# control_AX12.net
KiCad netlist of a schematic drawn in EAGLE
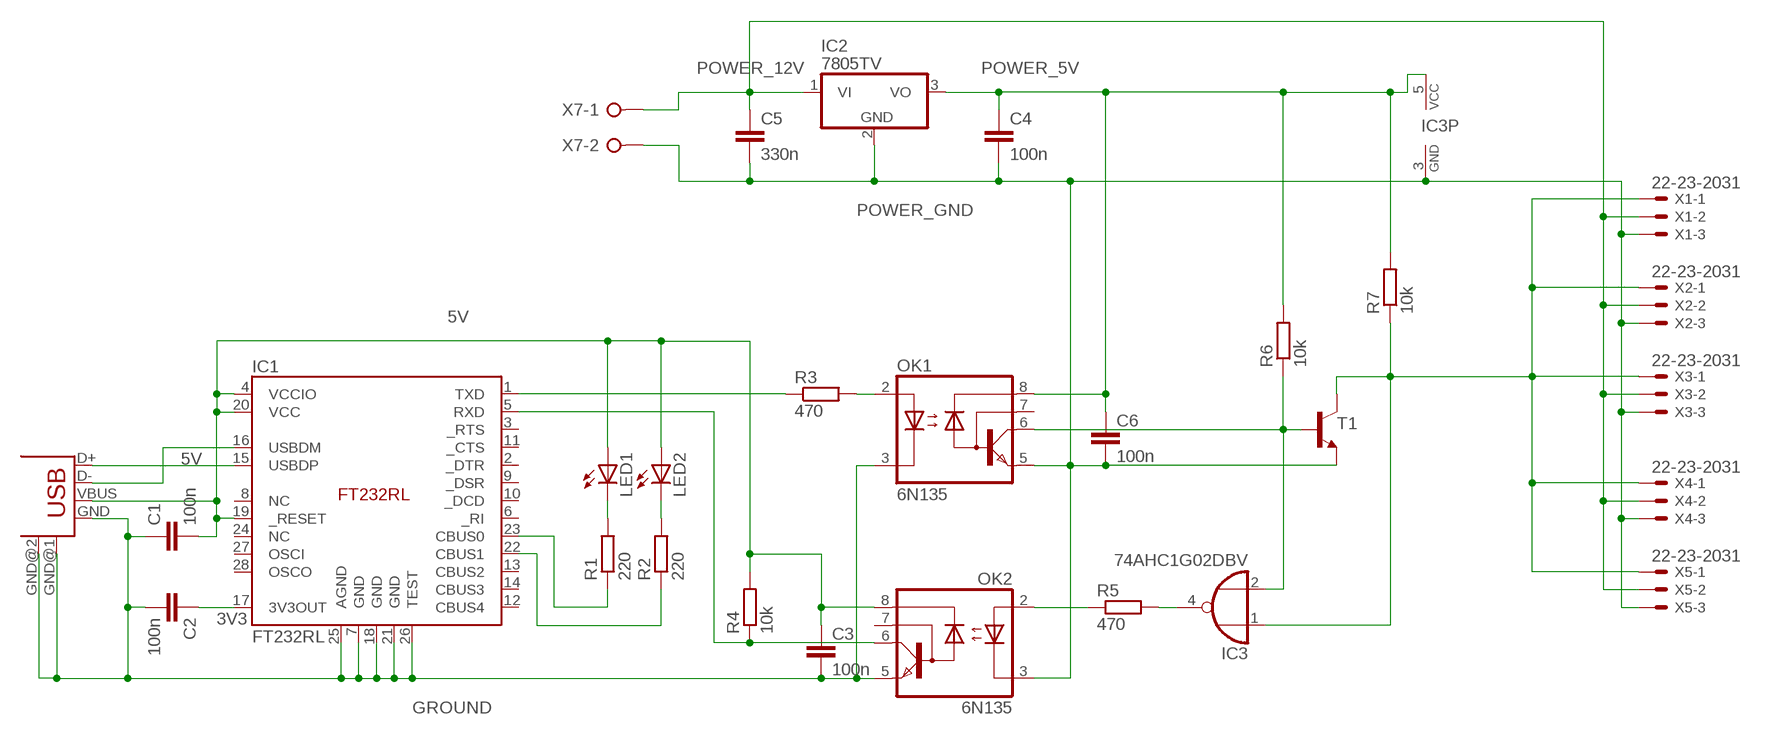
[diagram p0: schematic, sheet 1]

(export (version "E")
  (design (tool "Eeschema 10.0.6"))
  (components
    (comp (ref "C1")
      (value "100n")
      (footprint "eagle-import:C0805")
      (libsource (lib "eagle-import") (part "C-EUC0805"))
    )
    (comp (ref "C2")
      (value "100n")
      (footprint "eagle-import:C0805")
      (libsource (lib "eagle-import") (part "C-EUC0805"))
    )
    (comp (ref "C3")
      (value "100n")
      (footprint "eagle-import:C0805")
      (libsource (lib "eagle-import") (part "C-EUC0805"))
    )
    (comp (ref "C4")
      (value "100n")
      (footprint "eagle-import:C0805")
      (libsource (lib "eagle-import") (part "C-EUC0805"))
    )
    (comp (ref "C5")
      (value "330n")
      (footprint "eagle-import:C0805")
      (libsource (lib "eagle-import") (part "C-EUC0805"))
    )
    (comp (ref "C6")
      (value "100n")
      (footprint "eagle-import:C0805")
      (libsource (lib "eagle-import") (part "C-EUC0805"))
    )
    (comp (ref "IC1")
      (value "FT232RL")
      (footprint "eagle-import:SSOP-28")
      (libsource (lib "eagle-import") (part "FT232RL"))
    )
    (comp (ref "IC2")
      (value "7805TV")
      (footprint "eagle-import:TO220V")
      (libsource (lib "eagle-import") (part "78TV05"))
    )
    (comp (ref "IC3")
      (value "74AHC1G02DBV")
      (footprint "eagle-import:SOT23-5")
      (libsource (lib "eagle-import") (part "741G02DBVAHC"))
    )
    (comp (ref "LED1")
      (value "LED5MM")
      (footprint "eagle-import:LED5MM")
      (libsource (lib "eagle-import") (part "LED5MM"))
    )
    (comp (ref "LED2")
      (value "LED5MM")
      (footprint "eagle-import:LED5MM")
      (libsource (lib "eagle-import") (part "LED5MM"))
    )
    (comp (ref "OK1")
      (value "6N135")
      (footprint "eagle-import:DIL08")
      (fields (field (name "MF") "FAIRCHILD SEMICONDUCTOR"))
      (libsource (lib "eagle-import") (part "6N135"))
    )
    (comp (ref "OK2")
      (value "6N135")
      (footprint "eagle-import:DIL08")
      (fields (field (name "MF") "FAIRCHILD SEMICONDUCTOR"))
      (libsource (lib "eagle-import") (part "6N135"))
    )
    (comp (ref "R1")
      (value "220")
      (footprint "eagle-import:M0805")
      (libsource (lib "eagle-import") (part "resistor_R-EU_M0805"))
    )
    (comp (ref "R2")
      (value "220")
      (footprint "eagle-import:M0805")
      (libsource (lib "eagle-import") (part "resistor_R-EU_M0805"))
    )
    (comp (ref "R3")
      (value "470")
      (footprint "eagle-import:0207_10")
      (libsource (lib "eagle-import") (part "R-EU_0207/10"))
    )
    (comp (ref "R4")
      (value "10k")
      (footprint "eagle-import:0207_10")
      (libsource (lib "eagle-import") (part "R-EU_0207/10"))
    )
    (comp (ref "R5")
      (value "470")
      (footprint "eagle-import:0207_10")
      (libsource (lib "eagle-import") (part "R-EU_0207/10"))
    )
    (comp (ref "R6")
      (value "10k")
      (footprint "eagle-import:0207_10")
      (libsource (lib "eagle-import") (part "R-EU_0207/10"))
    )
    (comp (ref "R7")
      (value "10k")
      (footprint "eagle-import:0207_10")
      (libsource (lib "eagle-import") (part "R-EU_0207/10"))
    )
    (comp (ref "T1")
      (value "BC547-NPN-TO92-CBE")
      (footprint "eagle-import:TO92-CBE")
      (libsource (lib "eagle-import") (part "-NPN-TO92-CBEBC547"))
    )
    (comp (ref "USB1")
      (value "USB-B-H")
      (footprint "eagle-import:USB-B-H")
      (libsource (lib "eagle-import") (part "USB-B-H"))
    )
    (comp (ref "X1")
      (value "22-23-2031")
      (footprint "eagle-import:22-23-2031")
      (fields (field (name "MF") "MOLEX"))
      (libsource (lib "eagle-import") (part "22-23-2031"))
    )
    (comp (ref "X2")
      (value "22-23-2031")
      (footprint "eagle-import:22-23-2031")
      (fields (field (name "MF") "MOLEX"))
      (libsource (lib "eagle-import") (part "22-23-2031"))
    )
    (comp (ref "X3")
      (value "22-23-2031")
      (footprint "eagle-import:22-23-2031")
      (fields (field (name "MF") "MOLEX"))
      (libsource (lib "eagle-import") (part "22-23-2031"))
    )
    (comp (ref "X4")
      (value "22-23-2031")
      (footprint "eagle-import:22-23-2031")
      (fields (field (name "MF") "MOLEX"))
      (libsource (lib "eagle-import") (part "22-23-2031"))
    )
    (comp (ref "X5")
      (value "22-23-2031")
      (footprint "eagle-import:22-23-2031")
      (fields (field (name "MF") "MOLEX"))
      (libsource (lib "eagle-import") (part "22-23-2031"))
    )
    (comp (ref "X7")
      (value "W237-02P")
      (footprint "eagle-import:W237-132")
      (libsource (lib "eagle-import") (part "W237-02P"))
    )
  )
  (nets
    (net (code "1") (name "/3V3") (class "Default")
      (node (ref "C2") (pin "1") (pinfunction "1_1") (pintype "passive"))
      (node (ref "IC1") (pin "17") (pinfunction "3V3OUT_17") (pintype "output"))
    )
    (net (code "2") (name "/5V") (class "Default")
      (node (ref "C1") (pin "2") (pinfunction "2_2") (pintype "passive"))
      (node (ref "C3") (pin "1") (pinfunction "1_1") (pintype "passive"))
      (node (ref "IC1") (pin "19") (pinfunction "_RESET_19") (pintype "input"))
      (node (ref "IC1") (pin "20") (pinfunction "VCC_20") (pintype "power_in"))
      (node (ref "IC1") (pin "4") (pinfunction "VCCIO_4") (pintype "power_in"))
      (node (ref "LED1") (pin "A") (pinfunction "A_A") (pintype "passive"))
      (node (ref "LED2") (pin "A") (pinfunction "A_A") (pintype "passive"))
      (node (ref "OK2") (pin "8") (pinfunction "VCC_8") (pintype "passive"))
      (node (ref "R4") (pin "2") (pinfunction "2_2") (pintype "passive"))
      (node (ref "USB1") (pin "VBUS") (pinfunction "VBUS_VBUS") (pintype "bidirectional"))
    )
    (net (code "3") (name "/GROUND") (class "Default")
      (node (ref "C1") (pin "1") (pinfunction "1_1") (pintype "passive"))
      (node (ref "C2") (pin "2") (pinfunction "2_2") (pintype "passive"))
      (node (ref "C3") (pin "2") (pinfunction "2_2") (pintype "passive"))
      (node (ref "IC1") (pin "18") (pinfunction "GND_18") (pintype "power_in"))
      (node (ref "IC1") (pin "21") (pinfunction "GND_21") (pintype "power_in"))
      (node (ref "IC1") (pin "25") (pinfunction "AGND_25") (pintype "power_in"))
      (node (ref "IC1") (pin "26") (pinfunction "TEST_26") (pintype "bidirectional"))
      (node (ref "IC1") (pin "7") (pinfunction "GND_7") (pintype "power_in"))
      (node (ref "OK1") (pin "3") (pinfunction "C_3") (pintype "passive"))
      (node (ref "OK2") (pin "5") (pinfunction "GND_5") (pintype "passive"))
      (node (ref "USB1") (pin "GND") (pinfunction "GND_GND") (pintype "bidirectional"))
      (node (ref "USB1") (pin "GND@1") (pinfunction "GND_GND@1") (pintype "bidirectional"))
      (node (ref "USB1") (pin "GND@2") (pinfunction "GND_GND@2") (pintype "bidirectional"))
    )
    (net (code "4") (name "/POWER_5V") (class "Default")
      (node (ref "C4") (pin "1") (pinfunction "1_1") (pintype "passive"))
      (node (ref "C6") (pin "1") (pinfunction "1_1") (pintype "passive"))
      (node (ref "IC2") (pin "3") (pinfunction "VO_3") (pintype "passive"))
      (node (ref "IC3") (pin "5") (pinfunction "VCC_5") (pintype "power_in"))
      (node (ref "OK1") (pin "8") (pinfunction "VCC_8") (pintype "passive"))
      (node (ref "R6") (pin "2") (pinfunction "2_2") (pintype "passive"))
      (node (ref "R7") (pin "2") (pinfunction "2_2") (pintype "passive"))
    )
    (net (code "5") (name "/POWER_12V") (class "Default")
      (node (ref "C5") (pin "1") (pinfunction "1_1") (pintype "passive"))
      (node (ref "IC2") (pin "1") (pinfunction "VI_1") (pintype "input"))
      (node (ref "X1") (pin "2") (pinfunction "S_2") (pintype "passive"))
      (node (ref "X2") (pin "2") (pinfunction "S_2") (pintype "passive"))
      (node (ref "X3") (pin "2") (pinfunction "S_2") (pintype "passive"))
      (node (ref "X4") (pin "2") (pinfunction "S_2") (pintype "passive"))
      (node (ref "X5") (pin "2") (pinfunction "S_2") (pintype "passive"))
      (node (ref "X7") (pin "1") (pinfunction "KL_1") (pintype "passive"))
    )
    (net (code "6") (name "/POWER_GND") (class "Default")
      (node (ref "C4") (pin "2") (pinfunction "2_2") (pintype "passive"))
      (node (ref "C5") (pin "2") (pinfunction "2_2") (pintype "passive"))
      (node (ref "C6") (pin "2") (pinfunction "2_2") (pintype "passive"))
      (node (ref "IC2") (pin "2") (pinfunction "GND_2") (pintype "passive"))
      (node (ref "IC3") (pin "3") (pinfunction "GND_3") (pintype "power_in"))
      (node (ref "OK1") (pin "5") (pinfunction "GND_5") (pintype "passive"))
      (node (ref "OK2") (pin "3") (pinfunction "C_3") (pintype "passive"))
      (node (ref "T1") (pin "E") (pinfunction "E_E") (pintype "passive"))
      (node (ref "X1") (pin "3") (pinfunction "S_3") (pintype "passive"))
      (node (ref "X2") (pin "3") (pinfunction "S_3") (pintype "passive"))
      (node (ref "X3") (pin "3") (pinfunction "S_3") (pintype "passive"))
      (node (ref "X4") (pin "3") (pinfunction "S_3") (pintype "passive"))
      (node (ref "X5") (pin "3") (pinfunction "S_3") (pintype "passive"))
      (node (ref "X7") (pin "2") (pinfunction "KL_2") (pintype "passive"))
    )
    (net (code "7") (name "Net-(IC1-CBUS0)") (class "Default")
      (node (ref "IC1") (pin "23") (pinfunction "CBUS0_23") (pintype "bidirectional"))
      (node (ref "R1") (pin "1") (pinfunction "1_1") (pintype "passive"))
    )
    (net (code "8") (name "Net-(IC1-CBUS1)") (class "Default")
      (node (ref "IC1") (pin "22") (pinfunction "CBUS1_22") (pintype "bidirectional"))
      (node (ref "R2") (pin "1") (pinfunction "1_1") (pintype "passive"))
    )
    (net (code "9") (name "Net-(IC1-RXD)") (class "Default")
      (node (ref "IC1") (pin "5") (pinfunction "RXD_5") (pintype "input"))
      (node (ref "OK2") (pin "6") (pinfunction "VO_6") (pintype "passive"))
      (node (ref "R4") (pin "1") (pinfunction "1_1") (pintype "passive"))
    )
    (net (code "10") (name "Net-(IC1-TXD)") (class "Default")
      (node (ref "IC1") (pin "1") (pinfunction "TXD_1") (pintype "output"))
      (node (ref "R3") (pin "1") (pinfunction "1_1") (pintype "passive"))
    )
    (net (code "11") (name "Net-(IC1-USBDM)") (class "Default")
      (node (ref "IC1") (pin "16") (pinfunction "USBDM_16") (pintype "bidirectional"))
      (node (ref "USB1") (pin "D-") (pinfunction "D-_D-") (pintype "bidirectional"))
    )
    (net (code "12") (name "Net-(IC1-USBDP)") (class "Default")
      (node (ref "IC1") (pin "15") (pinfunction "USBDP_15") (pintype "bidirectional"))
      (node (ref "USB1") (pin "D+") (pinfunction "D+_D+") (pintype "bidirectional"))
    )
    (net (code "13") (name "Net-(IC3A-I0)") (class "Default")
      (node (ref "IC3") (pin "1") (pinfunction "I0_1") (pintype "input"))
      (node (ref "R7") (pin "1") (pinfunction "1_1") (pintype "passive"))
      (node (ref "T1") (pin "C") (pinfunction "C_C") (pintype "passive"))
      (node (ref "X1") (pin "1") (pinfunction "S_1") (pintype "passive"))
      (node (ref "X2") (pin "1") (pinfunction "S_1") (pintype "passive"))
      (node (ref "X3") (pin "1") (pinfunction "S_1") (pintype "passive"))
      (node (ref "X4") (pin "1") (pinfunction "S_1") (pintype "passive"))
      (node (ref "X5") (pin "1") (pinfunction "S_1") (pintype "passive"))
    )
    (net (code "14") (name "Net-(IC3A-I1)") (class "Default")
      (node (ref "IC3") (pin "2") (pinfunction "I1_2") (pintype "input"))
      (node (ref "OK1") (pin "6") (pinfunction "VO_6") (pintype "passive"))
      (node (ref "R6") (pin "1") (pinfunction "1_1") (pintype "passive"))
      (node (ref "T1") (pin "B") (pinfunction "B_B") (pintype "passive"))
    )
    (net (code "15") (name "Net-(IC3A-O)") (class "Default")
      (node (ref "IC3") (pin "4") (pinfunction "O_4") (pintype "output"))
      (node (ref "R5") (pin "2") (pinfunction "2_2") (pintype "passive"))
    )
    (net (code "16") (name "Net-(LED1-C)") (class "Default")
      (node (ref "LED1") (pin "K") (pinfunction "C_K") (pintype "passive"))
      (node (ref "R1") (pin "2") (pinfunction "2_2") (pintype "passive"))
    )
    (net (code "17") (name "Net-(LED2-C)") (class "Default")
      (node (ref "LED2") (pin "K") (pinfunction "C_K") (pintype "passive"))
      (node (ref "R2") (pin "2") (pinfunction "2_2") (pintype "passive"))
    )
    (net (code "18") (name "Net-(OK1-A)") (class "Default")
      (node (ref "OK1") (pin "2") (pinfunction "A_2") (pintype "passive"))
      (node (ref "R3") (pin "2") (pinfunction "2_2") (pintype "passive"))
    )
    (net (code "19") (name "Net-(OK2-A)") (class "Default")
      (node (ref "OK2") (pin "2") (pinfunction "A_2") (pintype "passive"))
      (node (ref "R5") (pin "1") (pinfunction "1_1") (pintype "passive"))
    )
    (net (code "20") (name "unconnected-(IC1-CBUS2-Pad13)") (class "Default")
      (node (ref "IC1") (pin "13") (pinfunction "CBUS2_13") (pintype "bidirectional"))
    )
    (net (code "21") (name "unconnected-(IC1-CBUS3-Pad14)") (class "Default")
      (node (ref "IC1") (pin "14") (pinfunction "CBUS3_14") (pintype "bidirectional"))
    )
    (net (code "22") (name "unconnected-(IC1-CBUS4-Pad12)") (class "Default")
      (node (ref "IC1") (pin "12") (pinfunction "CBUS4_12") (pintype "bidirectional"))
    )
    (net (code "23") (name "unconnected-(IC1-NC-Pad8)") (class "Default")
      (node (ref "IC1") (pin "8") (pinfunction "NC_8") (pintype "no_connect"))
    )
    (net (code "24") (name "unconnected-(IC1-NC-Pad24)") (class "Default")
      (node (ref "IC1") (pin "24") (pinfunction "NC_24") (pintype "no_connect"))
    )
    (net (code "25") (name "unconnected-(IC1-OSCI-Pad27)") (class "Default")
      (node (ref "IC1") (pin "27") (pinfunction "OSCI_27") (pintype "input"))
    )
    (net (code "26") (name "unconnected-(IC1-OSCO-Pad28)") (class "Default")
      (node (ref "IC1") (pin "28") (pinfunction "OSCO_28") (pintype "output"))
    )
    (net (code "27") (name "unconnected-(IC1-_CTS-Pad11)") (class "Default")
      (node (ref "IC1") (pin "11") (pinfunction "_CTS_11") (pintype "input"))
    )
    (net (code "28") (name "unconnected-(IC1-_DCD-Pad10)") (class "Default")
      (node (ref "IC1") (pin "10") (pinfunction "_DCD_10") (pintype "input"))
    )
    (net (code "29") (name "unconnected-(IC1-_DSR-Pad9)") (class "Default")
      (node (ref "IC1") (pin "9") (pinfunction "_DSR_9") (pintype "input"))
    )
    (net (code "30") (name "unconnected-(IC1-_DTR-Pad2)") (class "Default")
      (node (ref "IC1") (pin "2") (pinfunction "_DTR_2") (pintype "input"))
    )
    (net (code "31") (name "unconnected-(IC1-_RI-Pad6)") (class "Default")
      (node (ref "IC1") (pin "6") (pinfunction "_RI_6") (pintype "input"))
    )
    (net (code "32") (name "unconnected-(IC1-_RTS-Pad3)") (class "Default")
      (node (ref "IC1") (pin "3") (pinfunction "_RTS_3") (pintype "output"))
    )
    (net (code "33") (name "unconnected-(OK1-VB-Pad7)") (class "Default")
      (node (ref "OK1") (pin "7") (pinfunction "VB_7") (pintype "passive"))
    )
    (net (code "34") (name "unconnected-(OK2-VB-Pad7)") (class "Default")
      (node (ref "OK2") (pin "7") (pinfunction "VB_7") (pintype "passive"))
    )
  )
)
